# max.net
KiCad netlist of a schematic drawn in Altium Designer
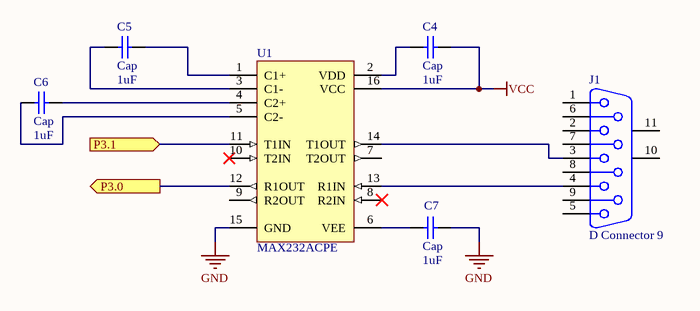
[diagram p0: max.SchDoc]

(export (version "E")
  (design (tool "Eeschema 10.0.6"))
  (components
    (comp (ref "C4")
      (value "Cap")
      (footprint "RAD-0.3")
      (description "Capacitor")
      (fields (field (name "ALTIUM_VALUE") "1uF") (field (name "PUBLISHER") "Altium Limited"))
      (libsource (lib "Miscellaneous Devices") (part "Cap"))
    )
    (comp (ref "C5")
      (value "Cap")
      (footprint "RAD-0.3")
      (description "Capacitor")
      (fields (field (name "ALTIUM_VALUE") "1uF") (field (name "PUBLISHER") "Altium Limited"))
      (libsource (lib "Miscellaneous Devices") (part "Cap"))
    )
    (comp (ref "C6")
      (value "Cap")
      (footprint "RAD-0.3")
      (description "Capacitor")
      (fields (field (name "ALTIUM_VALUE") "1uF") (field (name "PUBLISHER") "Altium Limited"))
      (libsource (lib "Miscellaneous Devices") (part "Cap"))
    )
    (comp (ref "C7")
      (value "Cap")
      (footprint "RAD-0.3")
      (description "Capacitor")
      (fields (field (name "ALTIUM_VALUE") "1uF") (field (name "PUBLISHER") "Altium Limited"))
      (libsource (lib "Miscellaneous Devices") (part "Cap"))
    )
    (comp (ref "J1")
      (value "D Connector 9")
      (footprint "DSUB1.385-2H9")
      (description "Receptacle Assembly, 9 Position, Right Angle")
      (fields (field (name "PUBLISHER") "Altium Limited"))
      (libsource (lib "Miscellaneous Connectors") (part "D Connector 9"))
    )
    (comp (ref "U1")
      (value "MAX232ACPE")
      (footprint "PE16A")
      (description "+5V Powered, Multi-Channel RS-232 Driver/Receiver")
      (fields (field (name "PUBLISHER") "Altium Limited"))
      (libsource (lib "Maxim Communication Transceiver") (part "MAX232ACPE"))
    )
  )
  (nets
    (net (code "1") (name "/P3.0") (class "Default")
      (node (ref "U1") (pin "12") (pinfunction "R1OUT_12") (pintype "output"))
    )
    (net (code "2") (name "/P3.1") (class "Default")
      (node (ref "U1") (pin "11") (pinfunction "T1IN_11") (pintype "input"))
    )
    (net (code "3") (name "GND") (class "Default")
      (node (ref "C7") (pin "2") (pinfunction "2_2") (pintype "passive"))
      (node (ref "U1") (pin "15") (pinfunction "GND_15") (pintype "power_in"))
    )
    (net (code "4") (name "Net-(U1-C1+)") (class "Default")
      (node (ref "C5") (pin "2") (pinfunction "2_2") (pintype "passive"))
      (node (ref "U1") (pin "1") (pinfunction "C1+_1") (pintype "passive"))
    )
    (net (code "5") (name "Net-(U1-C1-)") (class "Default")
      (node (ref "C5") (pin "1") (pinfunction "1_1") (pintype "passive"))
      (node (ref "U1") (pin "3") (pinfunction "C1-_3") (pintype "passive"))
    )
    (net (code "6") (name "Net-(U1-C2+)") (class "Default")
      (node (ref "C6") (pin "2") (pinfunction "2_2") (pintype "passive"))
      (node (ref "U1") (pin "4") (pinfunction "C2+_4") (pintype "passive"))
    )
    (net (code "7") (name "Net-(U1-C2-)") (class "Default")
      (node (ref "C6") (pin "1") (pinfunction "1_1") (pintype "passive"))
      (node (ref "U1") (pin "5") (pinfunction "C2-_5") (pintype "passive"))
    )
    (net (code "8") (name "Net-(U1-R1IN)") (class "Default")
      (node (ref "J1") (pin "4") (pinfunction "4_4") (pintype "passive"))
      (node (ref "U1") (pin "13") (pinfunction "R1IN_13") (pintype "input"))
    )
    (net (code "9") (name "Net-(U1-T1OUT)") (class "Default")
      (node (ref "J1") (pin "3") (pinfunction "3_3") (pintype "passive"))
      (node (ref "U1") (pin "14") (pinfunction "T1OUT_14") (pintype "output"))
    )
    (net (code "10") (name "Net-(U1-VDD)") (class "Default")
      (node (ref "C4") (pin "1") (pinfunction "1_1") (pintype "passive"))
      (node (ref "U1") (pin "2") (pinfunction "VDD_2") (pintype "power_in"))
    )
    (net (code "11") (name "Net-(U1-VEE)") (class "Default")
      (node (ref "C7") (pin "1") (pinfunction "1_1") (pintype "passive"))
      (node (ref "U1") (pin "6") (pinfunction "VEE_6") (pintype "power_in"))
    )
    (net (code "12") (name "VCC") (class "Default")
      (node (ref "C4") (pin "2") (pinfunction "2_2") (pintype "passive"))
      (node (ref "U1") (pin "16") (pinfunction "VCC_16") (pintype "power_in"))
    )
    (net (code "13") (name "unconnected-(J1-MH1-Pad10)") (class "Default")
      (node (ref "J1") (pin "10") (pinfunction "MH1_10") (pintype "passive"))
    )
    (net (code "14") (name "unconnected-(J1-MH2-Pad11)") (class "Default")
      (node (ref "J1") (pin "11") (pinfunction "MH2_11") (pintype "passive"))
    )
    (net (code "15") (name "unconnected-(J1-Pad1)") (class "Default")
      (node (ref "J1") (pin "1") (pinfunction "1_1") (pintype "passive"))
    )
    (net (code "16") (name "unconnected-(J1-Pad2)") (class "Default")
      (node (ref "J1") (pin "2") (pinfunction "2_2") (pintype "passive"))
    )
    (net (code "17") (name "unconnected-(J1-Pad5)") (class "Default")
      (node (ref "J1") (pin "5") (pinfunction "5_5") (pintype "passive"))
    )
    (net (code "18") (name "unconnected-(J1-Pad6)") (class "Default")
      (node (ref "J1") (pin "6") (pinfunction "6_6") (pintype "passive"))
    )
    (net (code "19") (name "unconnected-(J1-Pad7)") (class "Default")
      (node (ref "J1") (pin "7") (pinfunction "7_7") (pintype "passive"))
    )
    (net (code "20") (name "unconnected-(J1-Pad8)") (class "Default")
      (node (ref "J1") (pin "8") (pinfunction "8_8") (pintype "passive"))
    )
    (net (code "21") (name "unconnected-(J1-Pad9)") (class "Default")
      (node (ref "J1") (pin "9") (pinfunction "9_9") (pintype "passive"))
    )
    (net (code "22") (name "unconnected-(U1-R2IN-Pad8)") (class "Default")
      (node (ref "U1") (pin "8") (pinfunction "R2IN_8") (pintype "input+no_connect"))
    )
    (net (code "23") (name "unconnected-(U1-R2OUT-Pad9)") (class "Default")
      (node (ref "U1") (pin "9") (pinfunction "R2OUT_9") (pintype "output"))
    )
    (net (code "24") (name "unconnected-(U1-T2IN-Pad10)") (class "Default")
      (node (ref "U1") (pin "10") (pinfunction "T2IN_10") (pintype "input+no_connect"))
    )
    (net (code "25") (name "unconnected-(U1-T2OUT-Pad7)") (class "Default")
      (node (ref "U1") (pin "7") (pinfunction "T2OUT_7") (pintype "output"))
    )
  )
)
